# BeagleQ-v02.net
KiCad netlist of a schematic drawn in EAGLE
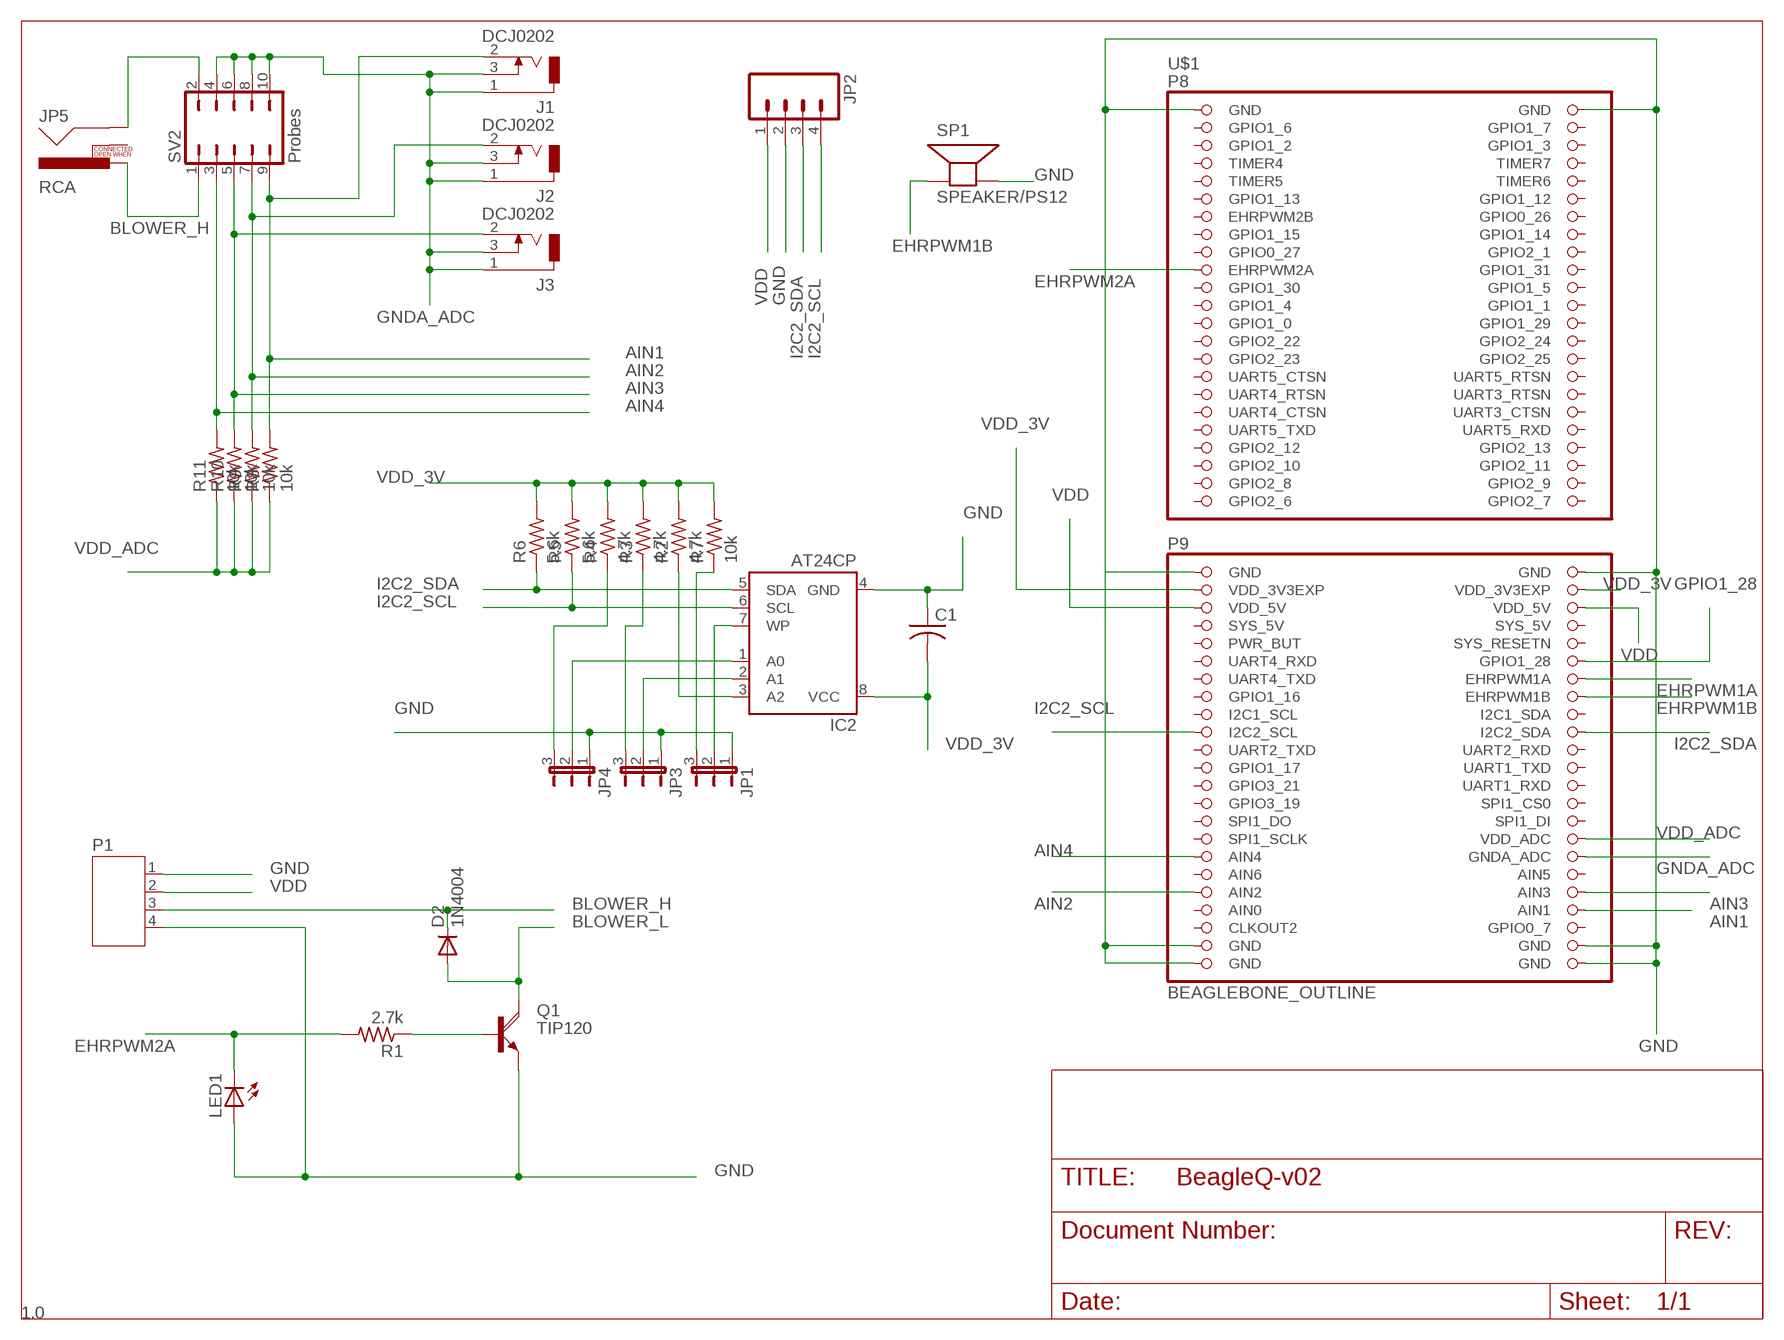
[diagram p0: schematic, sheet 1]

(export (version "E")
  (design (tool "Eeschema 10.0.6"))
  (components
    (comp (ref "C1")
      (value "C-US025-025X050")
      (footprint "eagle-import:C025-025X050")
      (libsource (lib "eagle-import") (part "C-US025-025X050"))
    )
    (comp (ref "D2")
      (value "1N4004")
      (footprint "eagle-import:DO41-10")
      (libsource (lib "eagle-import") (part "1N4004"))
    )
    (comp (ref "IC2")
      (value "AT24CP")
      (footprint "eagle-import:DIL08")
      (fields (field (name "MPN") "AT24C1024BW-SH-B"))
      (libsource (lib "eagle-import") (part "AT24CP"))
    )
    (comp (ref "J1")
      (value "DCJ0202")
      (footprint "eagle-import:DCJ0202")
      (libsource (lib "eagle-import") (part "DCJ0202"))
    )
    (comp (ref "J2")
      (value "DCJ0202")
      (footprint "eagle-import:DCJ0202")
      (libsource (lib "eagle-import") (part "DCJ0202"))
    )
    (comp (ref "J3")
      (value "DCJ0202")
      (footprint "eagle-import:DCJ0202")
      (libsource (lib "eagle-import") (part "DCJ0202"))
    )
    (comp (ref "JP1")
      (value "JP2E")
      (footprint "eagle-import:JP2")
      (libsource (lib "eagle-import") (part "JP2E"))
    )
    (comp (ref "JP2")
      (value "M04PTH")
      (footprint "eagle-import:1X04")
      (libsource (lib "eagle-import") (part "M04PTH"))
    )
    (comp (ref "JP3")
      (value "JP2E")
      (footprint "eagle-import:JP2")
      (libsource (lib "eagle-import") (part "JP2E"))
    )
    (comp (ref "JP4")
      (value "JP2E")
      (footprint "eagle-import:JP2")
      (libsource (lib "eagle-import") (part "JP2E"))
    )
    (comp (ref "JP5")
      (value "RCA")
      (footprint "eagle-import:RCA")
      (libsource (lib "eagle-import") (part "RCA"))
    )
    (comp (ref "LED1")
      (value "LED3MM")
      (footprint "eagle-import:LED3MM")
      (libsource (lib "eagle-import") (part "LED3MM"))
    )
    (comp (ref "P1")
      (value "JST-PH4")
      (footprint "eagle-import:JST-PH4")
      (libsource (lib "eagle-import") (part "JST-PH4"))
    )
    (comp (ref "Q1")
      (value "TIP120")
      (footprint "eagle-import:TO220AH")
      (libsource (lib "eagle-import") (part "TIP120"))
    )
    (comp (ref "R1")
      (value "2.7k")
      (footprint "eagle-import:0207_10")
      (libsource (lib "eagle-import") (part "R-US_0207/10"))
    )
    (comp (ref "R2")
      (value "4.7k")
      (footprint "eagle-import:0207_10")
      (libsource (lib "eagle-import") (part "R-US_0207/10"))
    )
    (comp (ref "R3")
      (value "4.7k")
      (footprint "eagle-import:0207_10")
      (libsource (lib "eagle-import") (part "R-US_0207/10"))
    )
    (comp (ref "R4")
      (value "4.7k")
      (footprint "eagle-import:0207_10")
      (libsource (lib "eagle-import") (part "R-US_0207/10"))
    )
    (comp (ref "R5")
      (value "5.6k")
      (footprint "eagle-import:0207_10")
      (libsource (lib "eagle-import") (part "R-US_0207/10"))
    )
    (comp (ref "R6")
      (value "5.6k")
      (footprint "eagle-import:0207_10")
      (libsource (lib "eagle-import") (part "R-US_0207/10"))
    )
    (comp (ref "R7")
      (value "10k")
      (footprint "eagle-import:0207_10")
      (libsource (lib "eagle-import") (part "R-US_0207/10"))
    )
    (comp (ref "R8")
      (value "10k")
      (footprint "eagle-import:0207_10")
      (libsource (lib "eagle-import") (part "R-US_0207/10"))
    )
    (comp (ref "R9")
      (value "10k")
      (footprint "eagle-import:0207_10")
      (libsource (lib "eagle-import") (part "R-US_0207/10"))
    )
    (comp (ref "R10")
      (value "10k")
      (footprint "eagle-import:0207_10")
      (libsource (lib "eagle-import") (part "R-US_0207/10"))
    )
    (comp (ref "R11")
      (value "10k")
      (footprint "eagle-import:0207_10")
      (libsource (lib "eagle-import") (part "R-US_0207/10"))
    )
    (comp (ref "SP1")
      (value "SPEAKER/PS12")
      (footprint "eagle-import:PS12")
      (libsource (lib "eagle-import") (part "SPEAKER/PS12"))
    )
    (comp (ref "SV2")
      (value "Probes")
      (footprint "eagle-import:JP5Q")
      (libsource (lib "eagle-import") (part "JP5Q"))
    )
    (comp (ref "U$1")
      (value "BEAGLEBONE_OUTLINE")
      (footprint "eagle-import:BEAGLEBONE_SHIELD")
      (libsource (lib "eagle-import") (part "BEAGLEBONE_OUTLINE"))
    )
  )
  (nets
    (net (code "1") (name "/AIN0") (class "Default")
      (node (ref "U$1") (pin "85") (pinfunction "AIN0_85") (pintype "power_in"))
    )
    (net (code "2") (name "/AIN1") (class "Default")
      (node (ref "J1") (pin "2") (pinfunction "2_2") (pintype "passive"))
      (node (ref "R8") (pin "2") (pinfunction "2_2") (pintype "passive"))
      (node (ref "SV2") (pin "9") (pinfunction "9_9") (pintype "passive"))
      (node (ref "U$1") (pin "86") (pinfunction "AIN1_86") (pintype "passive"))
    )
    (net (code "3") (name "/AIN2") (class "Default")
      (node (ref "J2") (pin "2") (pinfunction "2_2") (pintype "passive"))
      (node (ref "R9") (pin "2") (pinfunction "2_2") (pintype "passive"))
      (node (ref "SV2") (pin "7") (pinfunction "7_7") (pintype "passive"))
      (node (ref "U$1") (pin "83") (pinfunction "AIN2_83") (pintype "passive"))
    )
    (net (code "4") (name "/AIN3") (class "Default")
      (node (ref "J3") (pin "2") (pinfunction "2_2") (pintype "passive"))
      (node (ref "R10") (pin "2") (pinfunction "2_2") (pintype "passive"))
      (node (ref "SV2") (pin "5") (pinfunction "5_5") (pintype "passive"))
      (node (ref "U$1") (pin "84") (pinfunction "AIN3_84") (pintype "passive"))
    )
    (net (code "5") (name "/AIN4") (class "Default")
      (node (ref "R11") (pin "2") (pinfunction "2_2") (pintype "passive"))
      (node (ref "SV2") (pin "3") (pinfunction "3_3") (pintype "passive"))
      (node (ref "U$1") (pin "79") (pinfunction "AIN4_79") (pintype "passive"))
    )
    (net (code "6") (name "/BLOWER_H") (class "Default")
      (node (ref "D2") (pin "C") (pinfunction "C_C") (pintype "passive"))
      (node (ref "JP5") (pin "PIN") (pinfunction "PIN_PIN") (pintype "bidirectional"))
      (node (ref "P1") (pin "3") (pinfunction "3_3") (pintype "passive"))
      (node (ref "SV2") (pin "1") (pinfunction "1_1") (pintype "passive"))
    )
    (net (code "7") (name "/BLOWER_L") (class "Default")
      (node (ref "D2") (pin "A") (pinfunction "A_A") (pintype "passive"))
      (node (ref "JP5") (pin "SHELL") (pinfunction "SHELL_SHELL") (pintype "bidirectional"))
      (node (ref "Q1") (pin "C") (pinfunction "C_C") (pintype "passive"))
      (node (ref "SV2") (pin "2") (pinfunction "2_2") (pintype "passive"))
    )
    (net (code "8") (name "/EHRPWM1A") (class "Default")
      (node (ref "U$1") (pin "60") (pinfunction "EHRPWM1A_60") (pintype "passive"))
    )
    (net (code "9") (name "/EHRPWM1B") (class "Default")
      (node (ref "SP1") (pin "P$1") (pinfunction "+_P$1") (pintype "passive"))
      (node (ref "U$1") (pin "62") (pinfunction "EHRPWM1B_62") (pintype "passive"))
    )
    (net (code "10") (name "/EHRPWM2A") (class "Default")
      (node (ref "LED1") (pin "K") (pinfunction "C_K") (pintype "passive"))
      (node (ref "R1") (pin "2") (pinfunction "2_2") (pintype "passive"))
      (node (ref "U$1") (pin "19") (pinfunction "EHRPWM2A_19") (pintype "passive"))
    )
    (net (code "11") (name "/GND") (class "Default")
      (node (ref "C1") (pin "1") (pinfunction "1_1") (pintype "passive"))
      (node (ref "IC2") (pin "4") (pinfunction "GND_4") (pintype "power_in"))
      (node (ref "JP1") (pin "1") (pinfunction "1_1") (pintype "passive"))
      (node (ref "JP2") (pin "2") (pinfunction "2_2") (pintype "passive"))
      (node (ref "JP3") (pin "1") (pinfunction "1_1") (pintype "passive"))
      (node (ref "JP4") (pin "1") (pinfunction "1_1") (pintype "passive"))
      (node (ref "LED1") (pin "A") (pinfunction "A_A") (pintype "passive"))
      (node (ref "P1") (pin "1") (pinfunction "1_1") (pintype "passive"))
      (node (ref "P1") (pin "4") (pinfunction "4_4") (pintype "passive"))
      (node (ref "Q1") (pin "E") (pinfunction "E_E") (pintype "passive"))
      (node (ref "SP1") (pin "P$2") (pinfunction "-_P$2") (pintype "passive"))
      (node (ref "U$1") (pin "1") (pinfunction "GND_1") (pintype "power_in"))
      (node (ref "U$1") (pin "2") (pinfunction "GND_2") (pintype "power_in"))
      (node (ref "U$1") (pin "47") (pinfunction "GND_47") (pintype "power_in"))
      (node (ref "U$1") (pin "48") (pinfunction "GND_48") (pintype "power_in"))
      (node (ref "U$1") (pin "89") (pinfunction "GND_89") (pintype "power_in"))
      (node (ref "U$1") (pin "90") (pinfunction "GND_90") (pintype "power_in"))
      (node (ref "U$1") (pin "91") (pinfunction "GND_91") (pintype "power_in"))
      (node (ref "U$1") (pin "92") (pinfunction "GND_92") (pintype "power_in"))
    )
    (net (code "12") (name "/GNDA_ADC") (class "Default")
      (node (ref "J1") (pin "1") (pinfunction "1_1") (pintype "passive"))
      (node (ref "J1") (pin "3") (pinfunction "3_3") (pintype "passive"))
      (node (ref "J2") (pin "1") (pinfunction "1_1") (pintype "passive"))
      (node (ref "J2") (pin "3") (pinfunction "3_3") (pintype "passive"))
      (node (ref "J3") (pin "1") (pinfunction "1_1") (pintype "passive"))
      (node (ref "J3") (pin "3") (pinfunction "3_3") (pintype "passive"))
      (node (ref "SV2") (pin "10") (pinfunction "10_10") (pintype "passive"))
      (node (ref "SV2") (pin "4") (pinfunction "4_4") (pintype "passive"))
      (node (ref "SV2") (pin "6") (pinfunction "6_6") (pintype "passive"))
      (node (ref "SV2") (pin "8") (pinfunction "8_8") (pintype "passive"))
      (node (ref "U$1") (pin "80") (pinfunction "GNDA_ADC_80") (pintype "passive"))
    )
    (net (code "13") (name "/GPIO1_28") (class "Default")
      (node (ref "U$1") (pin "58") (pinfunction "GPIO1_28_58") (pintype "passive"))
    )
    (net (code "14") (name "/I2C2_SCL") (class "Default")
      (node (ref "IC2") (pin "6") (pinfunction "SCL_6") (pintype "bidirectional"))
      (node (ref "JP2") (pin "4") (pinfunction "4_4") (pintype "passive"))
      (node (ref "R5") (pin "1") (pinfunction "1_1") (pintype "passive"))
      (node (ref "U$1") (pin "65") (pinfunction "I2C2_SCL_65") (pintype "passive"))
    )
    (net (code "15") (name "/I2C2_SDA") (class "Default")
      (node (ref "IC2") (pin "5") (pinfunction "SDA_5") (pintype "bidirectional"))
      (node (ref "JP2") (pin "3") (pinfunction "3_3") (pintype "passive"))
      (node (ref "R6") (pin "1") (pinfunction "1_1") (pintype "passive"))
      (node (ref "U$1") (pin "66") (pinfunction "I2C2_SDA_66") (pintype "passive"))
    )
    (net (code "16") (name "/SYS_5V") (class "Default")
      (node (ref "U$1") (pin "53") (pinfunction "SYS_5V_53") (pintype "power_in"))
    )
    (net (code "17") (name "/VDD") (class "Default")
      (node (ref "JP2") (pin "1") (pinfunction "1_1") (pintype "passive"))
      (node (ref "P1") (pin "2") (pinfunction "2_2") (pintype "passive"))
      (node (ref "U$1") (pin "51") (pinfunction "VDD_5V_51") (pintype "power_in"))
      (node (ref "U$1") (pin "52") (pinfunction "VDD_5V_52") (pintype "power_in"))
    )
    (net (code "18") (name "/VDD_3V") (class "Default")
      (node (ref "C1") (pin "2") (pinfunction "2_2") (pintype "passive"))
      (node (ref "IC2") (pin "8") (pinfunction "VCC_8") (pintype "power_in"))
      (node (ref "R2") (pin "2") (pinfunction "2_2") (pintype "passive"))
      (node (ref "R3") (pin "2") (pinfunction "2_2") (pintype "passive"))
      (node (ref "R4") (pin "2") (pinfunction "2_2") (pintype "passive"))
      (node (ref "R5") (pin "2") (pinfunction "2_2") (pintype "passive"))
      (node (ref "R6") (pin "2") (pinfunction "2_2") (pintype "passive"))
      (node (ref "R7") (pin "2") (pinfunction "2_2") (pintype "passive"))
      (node (ref "U$1") (pin "49") (pinfunction "VDD_3V3EXP_49") (pintype "power_in"))
      (node (ref "U$1") (pin "50") (pinfunction "VDD_3V3EXP_50") (pintype "power_in"))
    )
    (net (code "19") (name "/VDD_ADC") (class "Default")
      (node (ref "R10") (pin "1") (pinfunction "1_1") (pintype "passive"))
      (node (ref "R11") (pin "1") (pinfunction "1_1") (pintype "passive"))
      (node (ref "R8") (pin "1") (pinfunction "1_1") (pintype "passive"))
      (node (ref "R9") (pin "1") (pinfunction "1_1") (pintype "passive"))
      (node (ref "U$1") (pin "78") (pinfunction "VDD_ADC_78") (pintype "passive"))
    )
    (net (code "20") (name "Net-(IC2-A0)") (class "Default")
      (node (ref "IC2") (pin "1") (pinfunction "A0_1") (pintype "input"))
      (node (ref "JP4") (pin "2") (pinfunction "2_2") (pintype "passive"))
    )
    (net (code "21") (name "Net-(IC2-A1)") (class "Default")
      (node (ref "IC2") (pin "2") (pinfunction "A1_2") (pintype "input"))
      (node (ref "JP3") (pin "2") (pinfunction "2_2") (pintype "passive"))
    )
    (net (code "22") (name "Net-(IC2-A2)") (class "Default")
      (node (ref "IC2") (pin "3") (pinfunction "A2_3") (pintype "input"))
      (node (ref "R2") (pin "1") (pinfunction "1_1") (pintype "passive"))
    )
    (net (code "23") (name "Net-(IC2-WP)") (class "Default")
      (node (ref "IC2") (pin "7") (pinfunction "WP_7") (pintype "input"))
      (node (ref "JP1") (pin "2") (pinfunction "2_2") (pintype "passive"))
    )
    (net (code "24") (name "Net-(JP1-Pad3)") (class "Default")
      (node (ref "JP1") (pin "3") (pinfunction "3_3") (pintype "passive"))
      (node (ref "R7") (pin "1") (pinfunction "1_1") (pintype "passive"))
    )
    (net (code "25") (name "Net-(JP3-Pad3)") (class "Default")
      (node (ref "JP3") (pin "3") (pinfunction "3_3") (pintype "passive"))
      (node (ref "R3") (pin "1") (pinfunction "1_1") (pintype "passive"))
    )
    (net (code "26") (name "Net-(JP4-Pad3)") (class "Default")
      (node (ref "JP4") (pin "3") (pinfunction "3_3") (pintype "passive"))
      (node (ref "R4") (pin "1") (pinfunction "1_1") (pintype "passive"))
    )
    (net (code "27") (name "Net-(Q1-PadB)") (class "Default")
      (node (ref "Q1") (pin "B") (pinfunction "B_B") (pintype "passive"))
      (node (ref "R1") (pin "1") (pinfunction "1_1") (pintype "passive"))
    )
    (net (code "28") (name "unconnected-(JP5-PadSWITCH)") (class "Default")
      (node (ref "JP5") (pin "SWITCH") (pinfunction "SWITCH_SWITCH") (pintype "bidirectional"))
    )
    (net (code "29") (name "unconnected-(U$1-AIN5-Pad82)") (class "Default")
      (node (ref "U$1") (pin "82") (pinfunction "AIN5_82") (pintype "passive"))
    )
    (net (code "30") (name "unconnected-(U$1-AIN6-Pad81)") (class "Default")
      (node (ref "U$1") (pin "81") (pinfunction "AIN6_81") (pintype "passive"))
    )
    (net (code "31") (name "unconnected-(U$1-CLKOUT2-Pad87)") (class "Default")
      (node (ref "U$1") (pin "87") (pinfunction "CLKOUT2_87") (pintype "input"))
    )
    (net (code "32") (name "unconnected-(U$1-EHRPWM2B-Pad13)") (class "Default")
      (node (ref "U$1") (pin "13") (pinfunction "EHRPWM2B_13") (pintype "passive"))
    )
    (net (code "33") (name "unconnected-(U$1-GPIO0_7-Pad88)") (class "Default")
      (node (ref "U$1") (pin "88") (pinfunction "GPIO0_7_88") (pintype "passive"))
    )
    (net (code "34") (name "unconnected-(U$1-GPIO0_26-Pad14)") (class "Default")
      (node (ref "U$1") (pin "14") (pinfunction "GPIO0_26_14") (pintype "passive"))
    )
    (net (code "35") (name "unconnected-(U$1-GPIO0_27-Pad17)") (class "Default")
      (node (ref "U$1") (pin "17") (pinfunction "GPIO0_27_17") (pintype "passive"))
    )
    (net (code "36") (name "unconnected-(U$1-GPIO1_0-Pad25)") (class "Default")
      (node (ref "U$1") (pin "25") (pinfunction "GPIO1_0_25") (pintype "passive"))
    )
    (net (code "37") (name "unconnected-(U$1-GPIO1_1-Pad24)") (class "Default")
      (node (ref "U$1") (pin "24") (pinfunction "GPIO1_1_24") (pintype "passive"))
    )
    (net (code "38") (name "unconnected-(U$1-GPIO1_2-Pad5)") (class "Default")
      (node (ref "U$1") (pin "5") (pinfunction "GPIO1_2_5") (pintype "passive"))
    )
    (net (code "39") (name "unconnected-(U$1-GPIO1_3-Pad6)") (class "Default")
      (node (ref "U$1") (pin "6") (pinfunction "GPIO1_3_6") (pintype "passive"))
    )
    (net (code "40") (name "unconnected-(U$1-GPIO1_4-Pad23)") (class "Default")
      (node (ref "U$1") (pin "23") (pinfunction "GPIO1_4_23") (pintype "passive"))
    )
    (net (code "41") (name "unconnected-(U$1-GPIO1_5-Pad22)") (class "Default")
      (node (ref "U$1") (pin "22") (pinfunction "GPIO1_5_22") (pintype "passive"))
    )
    (net (code "42") (name "unconnected-(U$1-GPIO1_6-Pad3)") (class "Default")
      (node (ref "U$1") (pin "3") (pinfunction "GPIO1_6_3") (pintype "passive"))
    )
    (net (code "43") (name "unconnected-(U$1-GPIO1_7-Pad4)") (class "Default")
      (node (ref "U$1") (pin "4") (pinfunction "GPIO1_7_4") (pintype "passive"))
    )
    (net (code "44") (name "unconnected-(U$1-GPIO1_12-Pad12)") (class "Default")
      (node (ref "U$1") (pin "12") (pinfunction "GPIO1_12_12") (pintype "passive"))
    )
    (net (code "45") (name "unconnected-(U$1-GPIO1_13-Pad11)") (class "Default")
      (node (ref "U$1") (pin "11") (pinfunction "GPIO1_13_11") (pintype "passive"))
    )
    (net (code "46") (name "unconnected-(U$1-GPIO1_14-Pad16)") (class "Default")
      (node (ref "U$1") (pin "16") (pinfunction "GPIO1_14_16") (pintype "passive"))
    )
    (net (code "47") (name "unconnected-(U$1-GPIO1_15-Pad15)") (class "Default")
      (node (ref "U$1") (pin "15") (pinfunction "GPIO1_15_15") (pintype "passive"))
    )
    (net (code "48") (name "unconnected-(U$1-GPIO1_16-Pad61)") (class "Default")
      (node (ref "U$1") (pin "61") (pinfunction "GPIO1_16_61") (pintype "passive"))
    )
    (net (code "49") (name "unconnected-(U$1-GPIO1_17-Pad69)") (class "Default")
      (node (ref "U$1") (pin "69") (pinfunction "GPIO1_17_69") (pintype "passive"))
    )
    (net (code "50") (name "unconnected-(U$1-GPIO1_29-Pad26)") (class "Default")
      (node (ref "U$1") (pin "26") (pinfunction "GPIO1_29_26") (pintype "passive"))
    )
    (net (code "51") (name "unconnected-(U$1-GPIO1_30-Pad21)") (class "Default")
      (node (ref "U$1") (pin "21") (pinfunction "GPIO1_30_21") (pintype "passive"))
    )
    (net (code "52") (name "unconnected-(U$1-GPIO1_31-Pad20)") (class "Default")
      (node (ref "U$1") (pin "20") (pinfunction "GPIO1_31_20") (pintype "passive"))
    )
    (net (code "53") (name "unconnected-(U$1-GPIO2_1-Pad18)") (class "Default")
      (node (ref "U$1") (pin "18") (pinfunction "GPIO2_1_18") (pintype "passive"))
    )
    (net (code "54") (name "unconnected-(U$1-GPIO2_6-Pad45)") (class "Default")
      (node (ref "U$1") (pin "45") (pinfunction "GPIO2_6_45") (pintype "passive"))
    )
    (net (code "55") (name "unconnected-(U$1-GPIO2_7-Pad46)") (class "Default")
      (node (ref "U$1") (pin "46") (pinfunction "GPIO2_7_46") (pintype "passive"))
    )
    (net (code "56") (name "unconnected-(U$1-GPIO2_8-Pad43)") (class "Default")
      (node (ref "U$1") (pin "43") (pinfunction "GPIO2_8_43") (pintype "passive"))
    )
    (net (code "57") (name "unconnected-(U$1-GPIO2_9-Pad44)") (class "Default")
      (node (ref "U$1") (pin "44") (pinfunction "GPIO2_9_44") (pintype "passive"))
    )
    (net (code "58") (name "unconnected-(U$1-GPIO2_10-Pad41)") (class "Default")
      (node (ref "U$1") (pin "41") (pinfunction "GPIO2_10_41") (pintype "passive"))
    )
    (net (code "59") (name "unconnected-(U$1-GPIO2_11-Pad42)") (class "Default")
      (node (ref "U$1") (pin "42") (pinfunction "GPIO2_11_42") (pintype "passive"))
    )
    (net (code "60") (name "unconnected-(U$1-GPIO2_12-Pad39)") (class "Default")
      (node (ref "U$1") (pin "39") (pinfunction "GPIO2_12_39") (pintype "passive"))
    )
    (net (code "61") (name "unconnected-(U$1-GPIO2_13-Pad40)") (class "Default")
      (node (ref "U$1") (pin "40") (pinfunction "GPIO2_13_40") (pintype "passive"))
    )
    (net (code "62") (name "unconnected-(U$1-GPIO2_22-Pad27)") (class "Default")
      (node (ref "U$1") (pin "27") (pinfunction "GPIO2_22_27") (pintype "passive"))
    )
    (net (code "63") (name "unconnected-(U$1-GPIO2_23-Pad29)") (class "Default")
      (node (ref "U$1") (pin "29") (pinfunction "GPIO2_23_29") (pintype "passive"))
    )
    (net (code "64") (name "unconnected-(U$1-GPIO2_24-Pad28)") (class "Default")
      (node (ref "U$1") (pin "28") (pinfunction "GPIO2_24_28") (pintype "passive"))
    )
    (net (code "65") (name "unconnected-(U$1-GPIO2_25-Pad30)") (class "Default")
      (node (ref "U$1") (pin "30") (pinfunction "GPIO2_25_30") (pintype "passive"))
    )
    (net (code "66") (name "unconnected-(U$1-GPIO3_19-Pad73)") (class "Default")
      (node (ref "U$1") (pin "73") (pinfunction "GPIO3_19_73") (pintype "passive"))
    )
    (net (code "67") (name "unconnected-(U$1-GPIO3_21-Pad71)") (class "Default")
      (node (ref "U$1") (pin "71") (pinfunction "GPIO3_21_71") (pintype "passive"))
    )
    (net (code "68") (name "unconnected-(U$1-I2C1_SCL-Pad63)") (class "Default")
      (node (ref "U$1") (pin "63") (pinfunction "I2C1_SCL_63") (pintype "passive"))
    )
    (net (code "69") (name "unconnected-(U$1-I2C1_SDA-Pad64)") (class "Default")
      (node (ref "U$1") (pin "64") (pinfunction "I2C1_SDA_64") (pintype "passive"))
    )
    (net (code "70") (name "unconnected-(U$1-PWR_BUT-Pad55)") (class "Default")
      (node (ref "U$1") (pin "55") (pinfunction "PWR_BUT_55") (pintype "passive"))
    )
    (net (code "71") (name "unconnected-(U$1-SPI1_CS0-Pad74)") (class "Default")
      (node (ref "U$1") (pin "74") (pinfunction "SPI1_CS0_74") (pintype "passive"))
    )
    (net (code "72") (name "unconnected-(U$1-SPI1_DI-Pad76)") (class "Default")
      (node (ref "U$1") (pin "76") (pinfunction "SPI1_DI_76") (pintype "passive"))
    )
    (net (code "73") (name "unconnected-(U$1-SPI1_DO-Pad75)") (class "Default")
      (node (ref "U$1") (pin "75") (pinfunction "SPI1_DO_75") (pintype "passive"))
    )
    (net (code "74") (name "unconnected-(U$1-SPI1_SCLK-Pad77)") (class "Default")
      (node (ref "U$1") (pin "77") (pinfunction "SPI1_SCLK_77") (pintype "passive"))
    )
    (net (code "75") (name "unconnected-(U$1-SYS_5V-Pad54)") (class "Default")
      (node (ref "U$1") (pin "54") (pinfunction "SYS_5V_54") (pintype "passive"))
    )
    (net (code "76") (name "unconnected-(U$1-SYS_RESETN-Pad56)") (class "Default")
      (node (ref "U$1") (pin "56") (pinfunction "SYS_RESETN_56") (pintype "passive"))
    )
    (net (code "77") (name "unconnected-(U$1-TIMER4-Pad7)") (class "Default")
      (node (ref "U$1") (pin "7") (pinfunction "TIMER4_7") (pintype "passive"))
    )
    (net (code "78") (name "unconnected-(U$1-TIMER5-Pad9)") (class "Default")
      (node (ref "U$1") (pin "9") (pinfunction "TIMER5_9") (pintype "passive"))
    )
    (net (code "79") (name "unconnected-(U$1-TIMER6-Pad10)") (class "Default")
      (node (ref "U$1") (pin "10") (pinfunction "TIMER6_10") (pintype "passive"))
    )
    (net (code "80") (name "unconnected-(U$1-TIMER7-Pad8)") (class "Default")
      (node (ref "U$1") (pin "8") (pinfunction "TIMER7_8") (pintype "passive"))
    )
    (net (code "81") (name "unconnected-(U$1-UART1_RXD-Pad72)") (class "Default")
      (node (ref "U$1") (pin "72") (pinfunction "UART1_RXD_72") (pintype "passive"))
    )
    (net (code "82") (name "unconnected-(U$1-UART1_TXD-Pad70)") (class "Default")
      (node (ref "U$1") (pin "70") (pinfunction "UART1_TXD_70") (pintype "passive"))
    )
    (net (code "83") (name "unconnected-(U$1-UART2_RXD-Pad68)") (class "Default")
      (node (ref "U$1") (pin "68") (pinfunction "UART2_RXD_68") (pintype "passive"))
    )
    (net (code "84") (name "unconnected-(U$1-UART2_TXD-Pad67)") (class "Default")
      (node (ref "U$1") (pin "67") (pinfunction "UART2_TXD_67") (pintype "passive"))
    )
    (net (code "85") (name "unconnected-(U$1-UART3_CTSN-Pad36)") (class "Default")
      (node (ref "U$1") (pin "36") (pinfunction "UART3_CTSN_36") (pintype "passive"))
    )
    (net (code "86") (name "unconnected-(U$1-UART3_RTSN-Pad34)") (class "Default")
      (node (ref "U$1") (pin "34") (pinfunction "UART3_RTSN_34") (pintype "passive"))
    )
    (net (code "87") (name "unconnected-(U$1-UART4_CTSN-Pad35)") (class "Default")
      (node (ref "U$1") (pin "35") (pinfunction "UART4_CTSN_35") (pintype "passive"))
    )
    (net (code "88") (name "unconnected-(U$1-UART4_RTSN-Pad33)") (class "Default")
      (node (ref "U$1") (pin "33") (pinfunction "UART4_RTSN_33") (pintype "passive"))
    )
    (net (code "89") (name "unconnected-(U$1-UART4_RXD-Pad57)") (class "Default")
      (node (ref "U$1") (pin "57") (pinfunction "UART4_RXD_57") (pintype "passive"))
    )
    (net (code "90") (name "unconnected-(U$1-UART4_TXD-Pad59)") (class "Default")
      (node (ref "U$1") (pin "59") (pinfunction "UART4_TXD_59") (pintype "passive"))
    )
    (net (code "91") (name "unconnected-(U$1-UART5_CTSN-Pad31)") (class "Default")
      (node (ref "U$1") (pin "31") (pinfunction "UART5_CTSN_31") (pintype "passive"))
    )
    (net (code "92") (name "unconnected-(U$1-UART5_RTSN-Pad32)") (class "Default")
      (node (ref "U$1") (pin "32") (pinfunction "UART5_RTSN_32") (pintype "passive"))
    )
    (net (code "93") (name "unconnected-(U$1-UART5_RXD-Pad38)") (class "Default")
      (node (ref "U$1") (pin "38") (pinfunction "UART5_RXD_38") (pintype "passive"))
    )
    (net (code "94") (name "unconnected-(U$1-UART5_TXD-Pad37)") (class "Default")
      (node (ref "U$1") (pin "37") (pinfunction "UART5_TXD_37") (pintype "passive"))
    )
  )
)
